# control-tu56v6.net
KiCad netlist of a schematic drawn in EAGLE
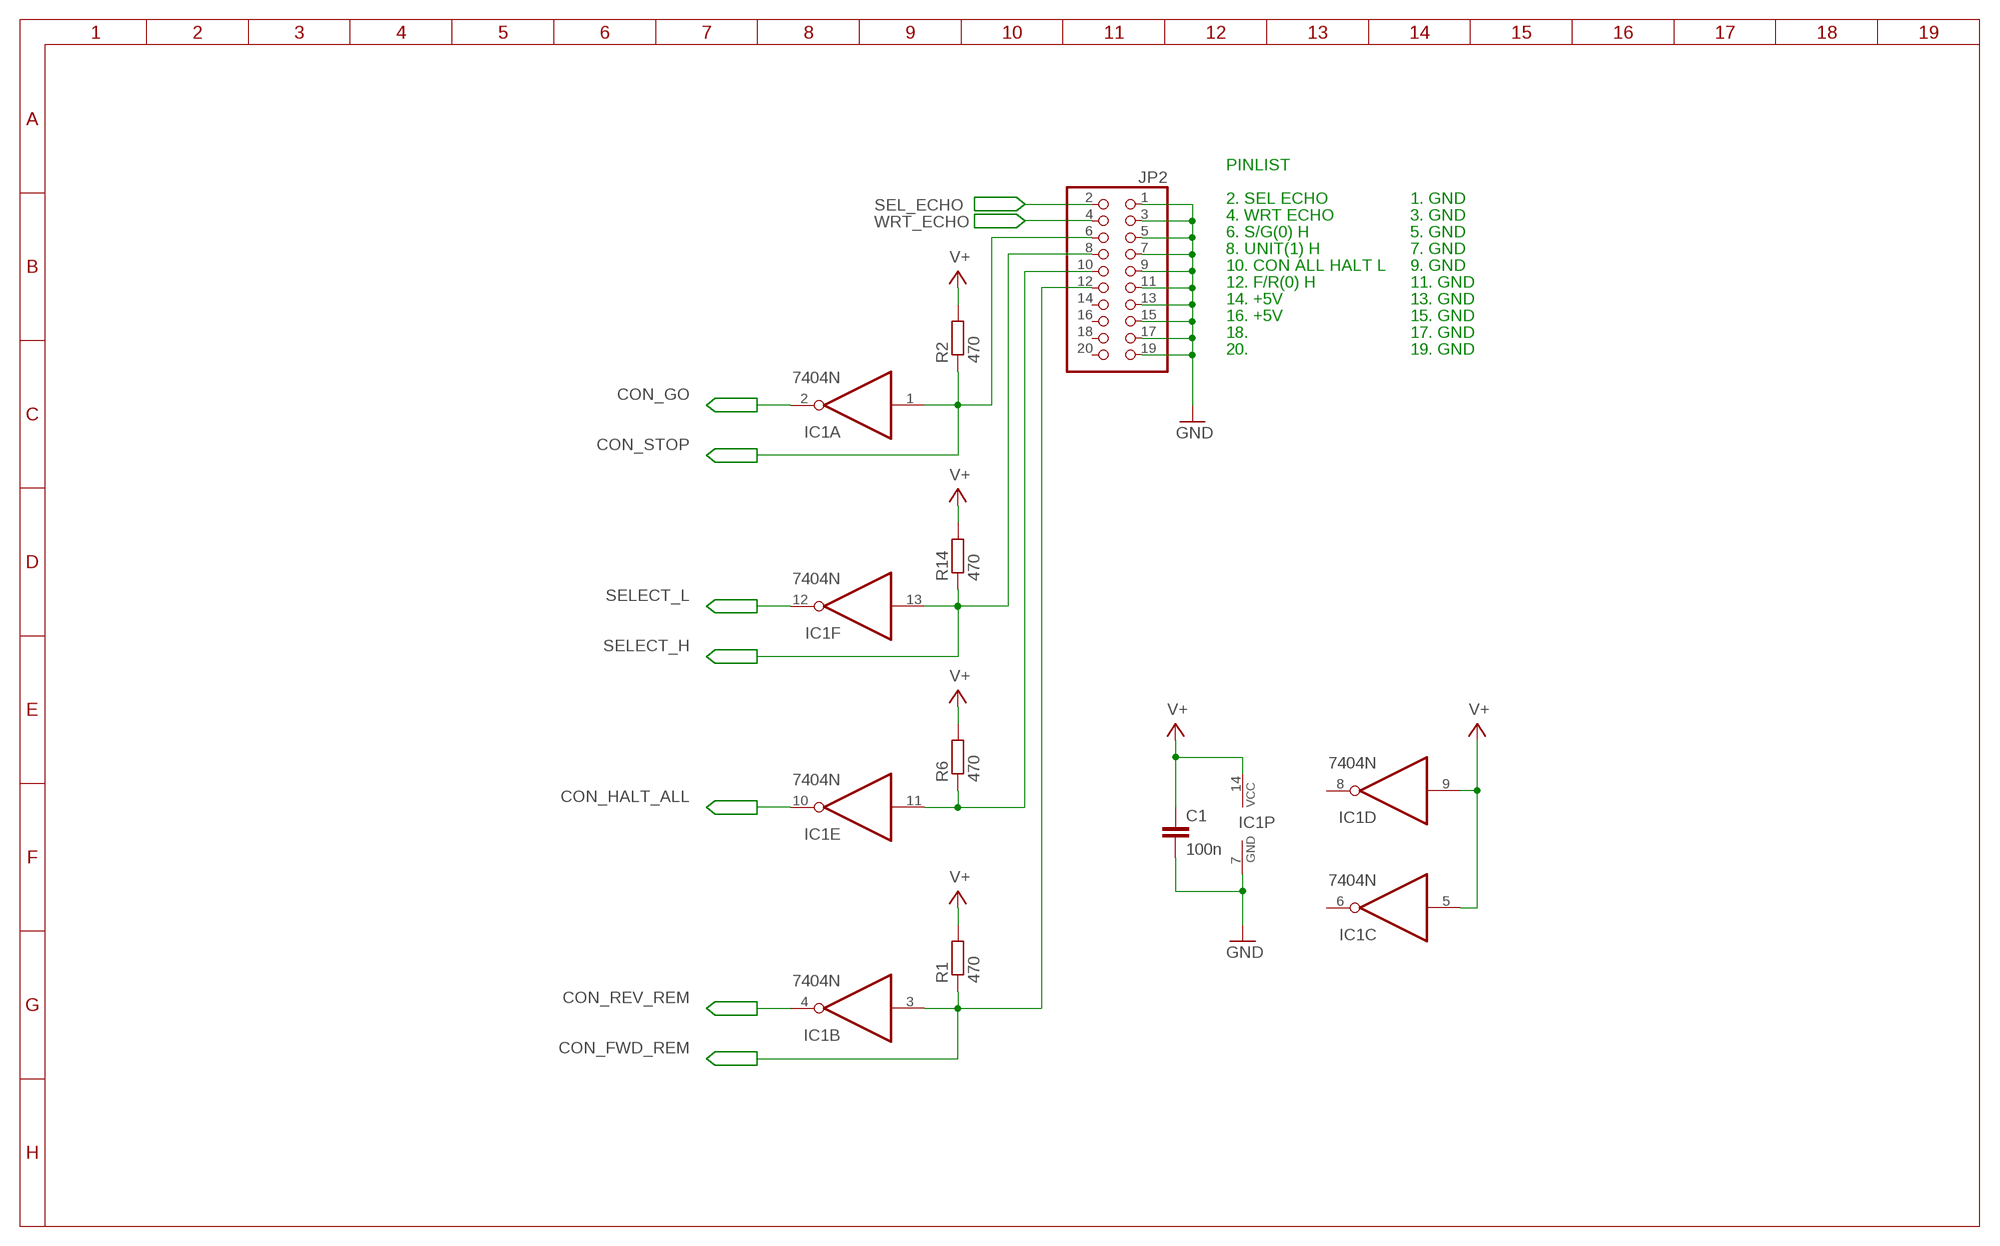
[diagram p0: schematic, sheet 1]
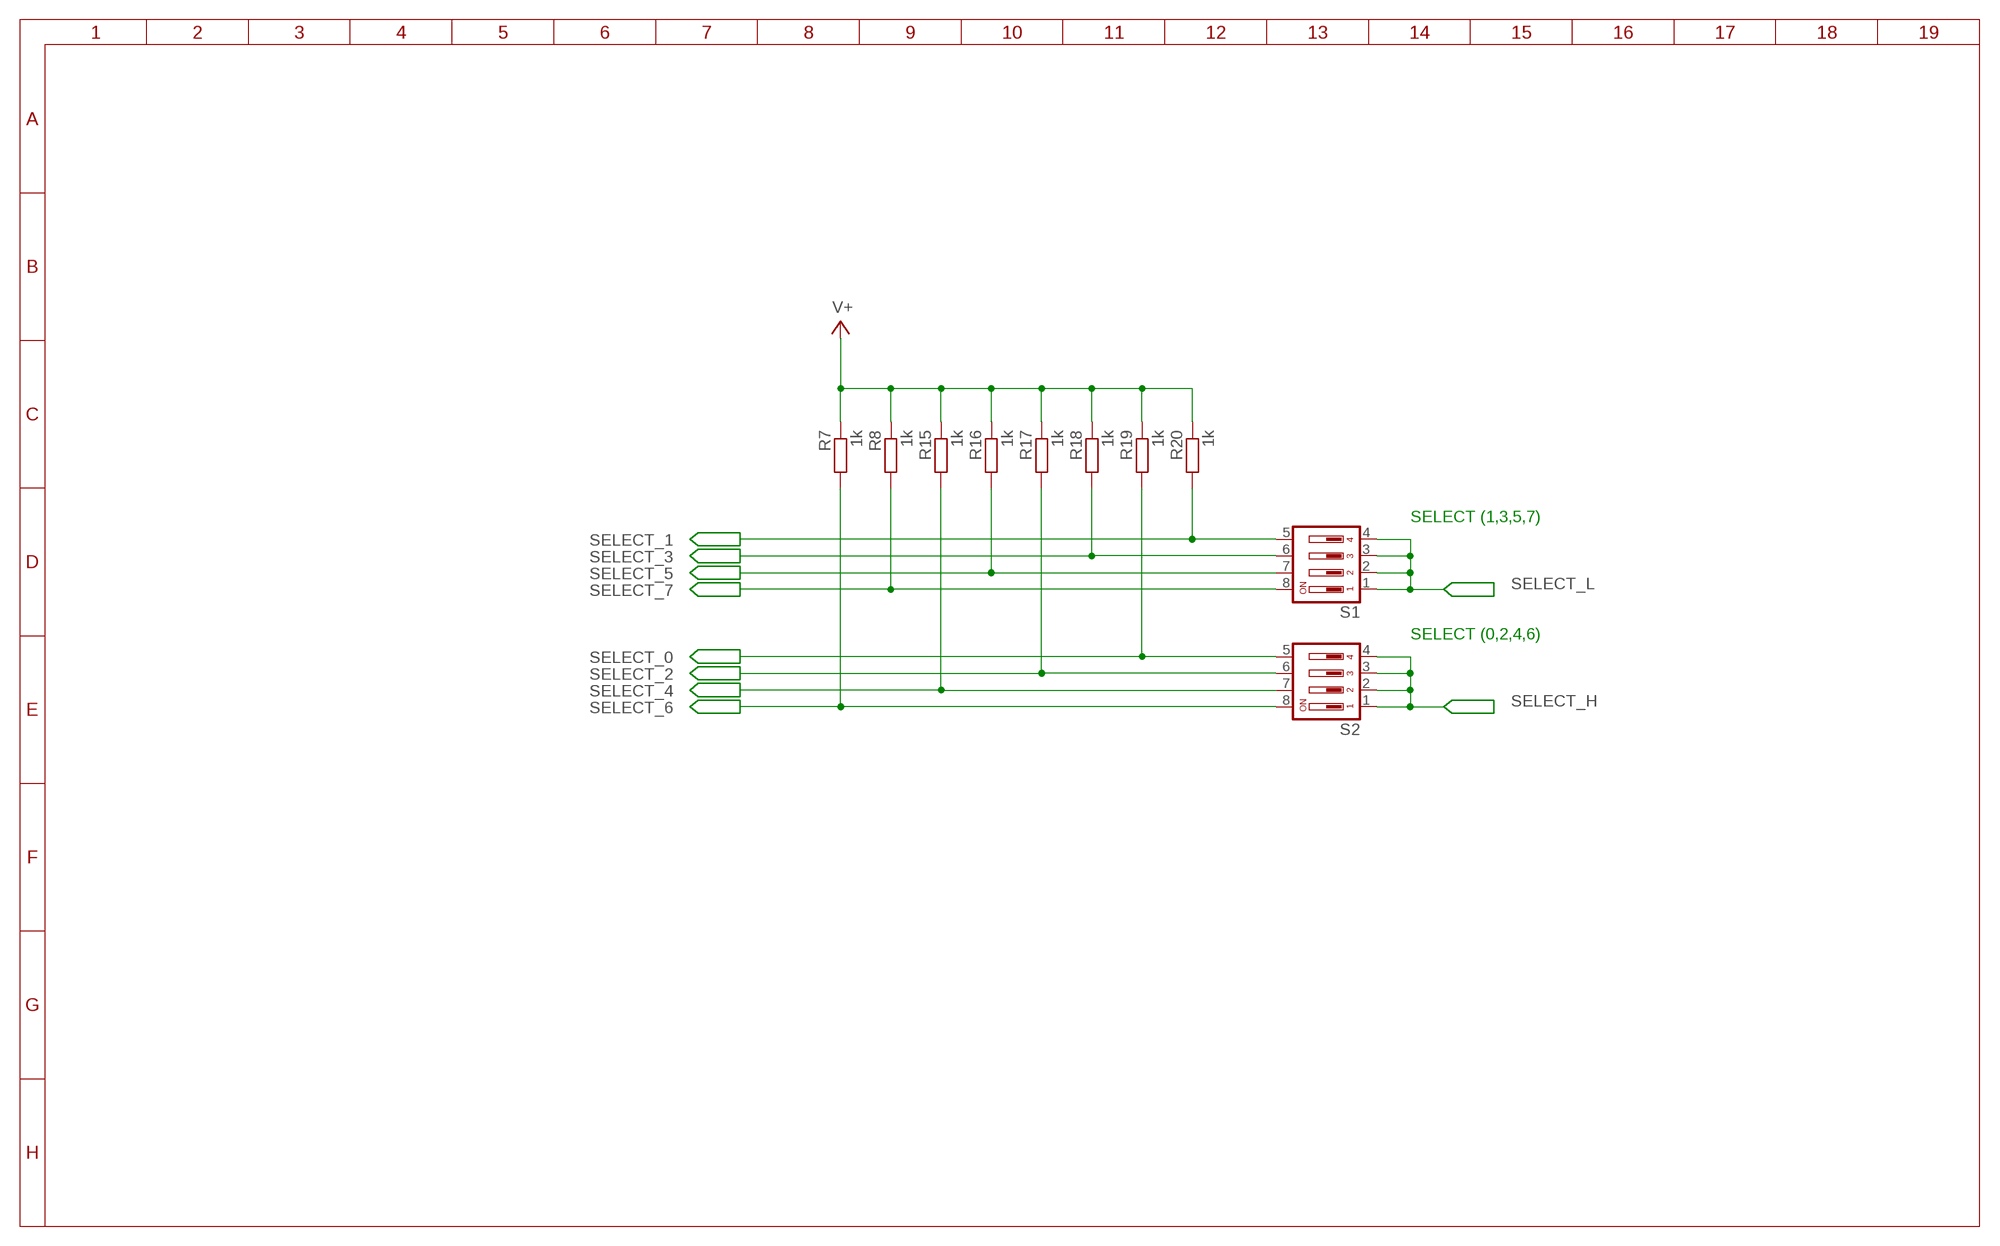
[diagram p1: schematic, sheet 2]
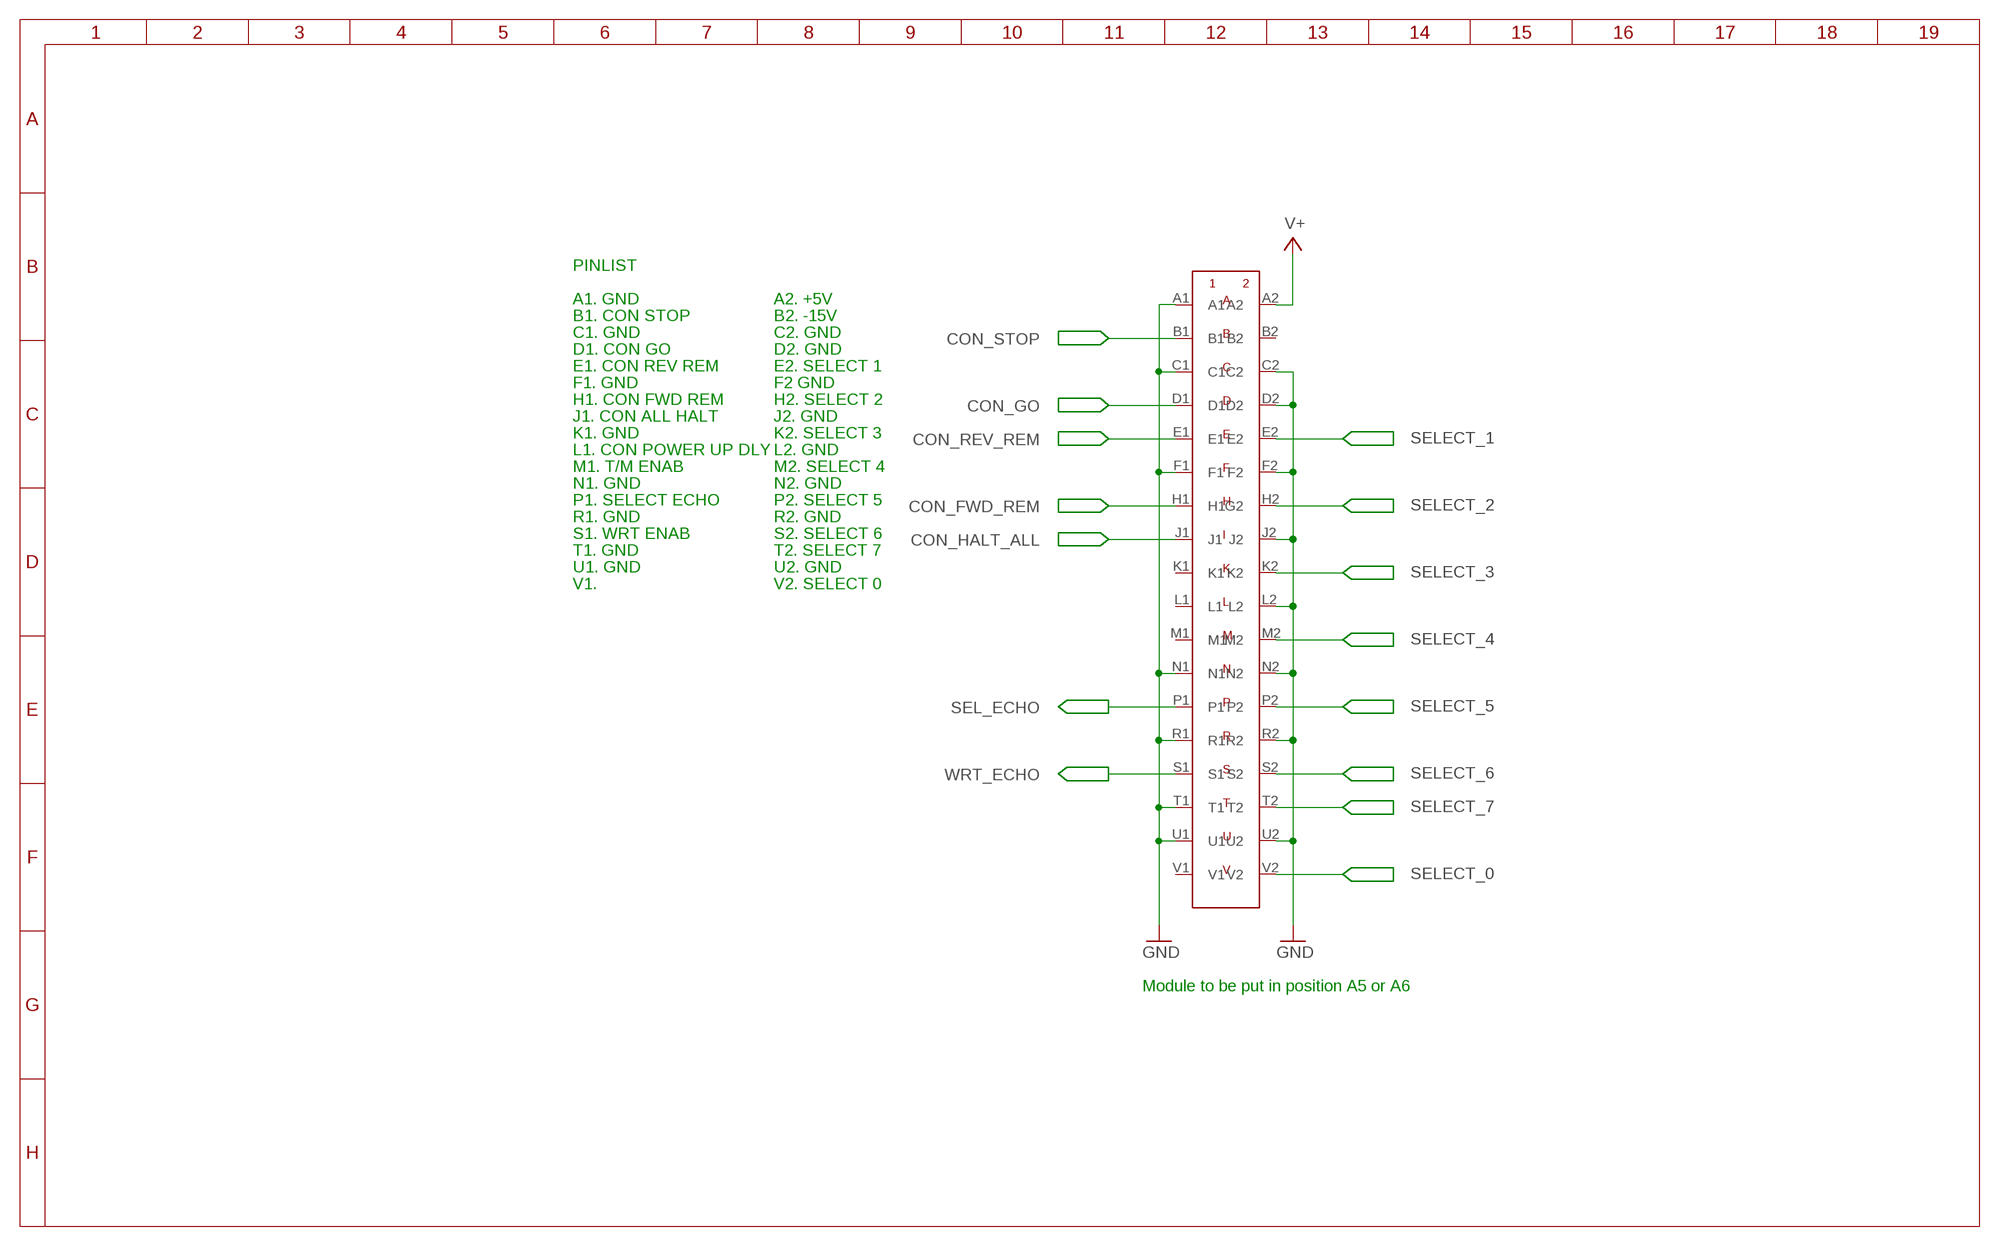
[diagram p2: schematic, sheet 3]

(export (version "E")
  (design (tool "Eeschema 10.0.6"))
  (components
    (comp (ref "CON1")
      (value "FLIPCHIP_1NORMAL")
      (footprint "eagle-import:FLIPCHIP-1")
      (libsource (lib "eagle-import") (part "FLIPCHIP_1NORMAL"))
    )
    (comp (ref "C1")
      (value "100n")
      (footprint "eagle-import:C5B3.5")
      (libsource (lib "eagle-import") (part "C5/3.5"))
    )
    (comp (ref "IC1")
      (value "7404N")
      (footprint "eagle-import:DIL14")
      (libsource (lib "eagle-import") (part "7404N"))
    )
    (comp (ref "JP2")
      (value "PINHD-2X10/90-FRAMED")
      (footprint "eagle-import:2Z10_90-FRAMED")
      (libsource (lib "eagle-import") (part "PINHD-2X10/90-FRAMED"))
    )
    (comp (ref "R1")
      (value "470")
      (footprint "eagle-import:0207_10")
      (libsource (lib "eagle-import") (part "R-EU_0207/10"))
    )
    (comp (ref "R2")
      (value "470")
      (footprint "eagle-import:0207_10")
      (libsource (lib "eagle-import") (part "R-EU_0207/10"))
    )
    (comp (ref "R6")
      (value "470")
      (footprint "eagle-import:0207_10")
      (libsource (lib "eagle-import") (part "R-EU_0207/10"))
    )
    (comp (ref "R14")
      (value "470")
      (footprint "eagle-import:0207_10")
      (libsource (lib "eagle-import") (part "R-EU_0207/10"))
    )
    (comp (ref "R7")
      (value "1k")
      (footprint "eagle-import:0207_10")
      (libsource (lib "eagle-import") (part "R-EU_0207/10"))
    )
    (comp (ref "R8")
      (value "1k")
      (footprint "eagle-import:0207_10")
      (libsource (lib "eagle-import") (part "R-EU_0207/10"))
    )
    (comp (ref "R15")
      (value "1k")
      (footprint "eagle-import:0207_10")
      (libsource (lib "eagle-import") (part "R-EU_0207/10"))
    )
    (comp (ref "R16")
      (value "1k")
      (footprint "eagle-import:0207_10")
      (libsource (lib "eagle-import") (part "R-EU_0207/10"))
    )
    (comp (ref "R17")
      (value "1k")
      (footprint "eagle-import:0207_10")
      (libsource (lib "eagle-import") (part "R-EU_0207/10"))
    )
    (comp (ref "R18")
      (value "1k")
      (footprint "eagle-import:0207_10")
      (libsource (lib "eagle-import") (part "R-EU_0207/10"))
    )
    (comp (ref "R19")
      (value "1k")
      (footprint "eagle-import:0207_10")
      (libsource (lib "eagle-import") (part "R-EU_0207/10"))
    )
    (comp (ref "R20")
      (value "1k")
      (footprint "eagle-import:0207_10")
      (libsource (lib "eagle-import") (part "R-EU_0207/10"))
    )
    (comp (ref "S1")
      (value "DIP04YL")
      (footprint "eagle-import:DIP04YL")
      (libsource (lib "eagle-import") (part "DIP04YL"))
    )
    (comp (ref "S2")
      (value "DIP04YL")
      (footprint "eagle-import:DIP04YL")
      (libsource (lib "eagle-import") (part "DIP04YL"))
    )
  )
  (nets
    (net (code "1") (name "CON_FWD_REM") (class "Default")
      (node (ref "CON1") (pin "H1") (pinfunction "H1_H1") (pintype "bidirectional"))
      (node (ref "IC1") (pin "3") (pinfunction "I_3") (pintype "input"))
      (node (ref "JP2") (pin "12") (pinfunction "12_12") (pintype "passive"))
      (node (ref "R1") (pin "1") (pinfunction "1_1") (pintype "passive"))
    )
    (net (code "2") (name "CON_GO") (class "Default")
      (node (ref "CON1") (pin "D1") (pinfunction "D1_D1") (pintype "bidirectional"))
      (node (ref "IC1") (pin "2") (pinfunction "O_2") (pintype "output"))
    )
    (net (code "3") (name "CON_HALT_ALL") (class "Default")
      (node (ref "CON1") (pin "J1") (pinfunction "J1_J1") (pintype "bidirectional"))
      (node (ref "IC1") (pin "10") (pinfunction "O_10") (pintype "output"))
    )
    (net (code "4") (name "CON_REV_REM") (class "Default")
      (node (ref "CON1") (pin "E1") (pinfunction "E1_E1") (pintype "bidirectional"))
      (node (ref "IC1") (pin "4") (pinfunction "O_4") (pintype "output"))
    )
    (net (code "5") (name "CON_STOP") (class "Default")
      (node (ref "CON1") (pin "B1") (pinfunction "B1_B1") (pintype "bidirectional"))
      (node (ref "IC1") (pin "1") (pinfunction "I_1") (pintype "input"))
      (node (ref "JP2") (pin "6") (pinfunction "6_6") (pintype "passive"))
      (node (ref "R2") (pin "1") (pinfunction "1_1") (pintype "passive"))
    )
    (net (code "6") (name "GND") (class "Default")
      (node (ref "C1") (pin "2") (pinfunction "2_2") (pintype "passive"))
      (node (ref "CON1") (pin "A1") (pinfunction "A1_A1") (pintype "bidirectional"))
      (node (ref "CON1") (pin "C1") (pinfunction "C1_C1") (pintype "bidirectional"))
      (node (ref "CON1") (pin "C2") (pinfunction "C2_C2") (pintype "bidirectional"))
      (node (ref "CON1") (pin "D2") (pinfunction "D2_D2") (pintype "bidirectional"))
      (node (ref "CON1") (pin "F1") (pinfunction "F1_F1") (pintype "bidirectional"))
      (node (ref "CON1") (pin "F2") (pinfunction "F2_F2") (pintype "bidirectional"))
      (node (ref "CON1") (pin "J2") (pinfunction "J2_J2") (pintype "bidirectional"))
      (node (ref "CON1") (pin "L2") (pinfunction "L2_L2") (pintype "bidirectional"))
      (node (ref "CON1") (pin "N1") (pinfunction "N1_N1") (pintype "bidirectional"))
      (node (ref "CON1") (pin "N2") (pinfunction "N2_N2") (pintype "bidirectional"))
      (node (ref "CON1") (pin "R1") (pinfunction "R1_R1") (pintype "bidirectional"))
      (node (ref "CON1") (pin "R2") (pinfunction "R2_R2") (pintype "bidirectional"))
      (node (ref "CON1") (pin "T1") (pinfunction "T1_T1") (pintype "bidirectional"))
      (node (ref "CON1") (pin "U1") (pinfunction "U1_U1") (pintype "bidirectional"))
      (node (ref "CON1") (pin "U2") (pinfunction "U2_U2") (pintype "bidirectional"))
      (node (ref "IC1") (pin "7") (pinfunction "GND_7") (pintype "power_in"))
      (node (ref "JP2") (pin "1") (pinfunction "1_1") (pintype "passive"))
      (node (ref "JP2") (pin "11") (pinfunction "11_11") (pintype "passive"))
      (node (ref "JP2") (pin "13") (pinfunction "13_13") (pintype "passive"))
      (node (ref "JP2") (pin "15") (pinfunction "15_15") (pintype "passive"))
      (node (ref "JP2") (pin "17") (pinfunction "17_17") (pintype "passive"))
      (node (ref "JP2") (pin "19") (pinfunction "19_19") (pintype "passive"))
      (node (ref "JP2") (pin "3") (pinfunction "3_3") (pintype "passive"))
      (node (ref "JP2") (pin "5") (pinfunction "5_5") (pintype "passive"))
      (node (ref "JP2") (pin "7") (pinfunction "7_7") (pintype "passive"))
      (node (ref "JP2") (pin "9") (pinfunction "9_9") (pintype "passive"))
    )
    (net (code "7") (name "Net-(IC1E-I)") (class "Default")
      (node (ref "IC1") (pin "11") (pinfunction "I_11") (pintype "input"))
      (node (ref "JP2") (pin "10") (pinfunction "10_10") (pintype "passive"))
      (node (ref "R6") (pin "1") (pinfunction "1_1") (pintype "passive"))
    )
    (net (code "8") (name "SELECT_0") (class "Default")
      (node (ref "CON1") (pin "V2") (pinfunction "V2_V2") (pintype "bidirectional"))
      (node (ref "R19") (pin "2") (pinfunction "2_2") (pintype "passive"))
      (node (ref "S2") (pin "5") (pinfunction "5_5") (pintype "passive"))
    )
    (net (code "9") (name "SELECT_1") (class "Default")
      (node (ref "CON1") (pin "E2") (pinfunction "E2_E2") (pintype "bidirectional"))
      (node (ref "R20") (pin "2") (pinfunction "2_2") (pintype "passive"))
      (node (ref "S1") (pin "5") (pinfunction "5_5") (pintype "passive"))
    )
    (net (code "10") (name "SELECT_2") (class "Default")
      (node (ref "CON1") (pin "H2") (pinfunction "G2_H2") (pintype "bidirectional"))
      (node (ref "R17") (pin "2") (pinfunction "2_2") (pintype "passive"))
      (node (ref "S2") (pin "6") (pinfunction "6_6") (pintype "passive"))
    )
    (net (code "11") (name "SELECT_3") (class "Default")
      (node (ref "CON1") (pin "K2") (pinfunction "K2_K2") (pintype "bidirectional"))
      (node (ref "R18") (pin "2") (pinfunction "2_2") (pintype "passive"))
      (node (ref "S1") (pin "6") (pinfunction "6_6") (pintype "passive"))
    )
    (net (code "12") (name "SELECT_4") (class "Default")
      (node (ref "CON1") (pin "M2") (pinfunction "M2_M2") (pintype "bidirectional"))
      (node (ref "R15") (pin "2") (pinfunction "2_2") (pintype "passive"))
      (node (ref "S2") (pin "7") (pinfunction "7_7") (pintype "passive"))
    )
    (net (code "13") (name "SELECT_5") (class "Default")
      (node (ref "CON1") (pin "P2") (pinfunction "P2_P2") (pintype "bidirectional"))
      (node (ref "R16") (pin "2") (pinfunction "2_2") (pintype "passive"))
      (node (ref "S1") (pin "7") (pinfunction "7_7") (pintype "passive"))
    )
    (net (code "14") (name "SELECT_6") (class "Default")
      (node (ref "CON1") (pin "S2") (pinfunction "S2_S2") (pintype "bidirectional"))
      (node (ref "R7") (pin "2") (pinfunction "2_2") (pintype "passive"))
      (node (ref "S2") (pin "8") (pinfunction "8_8") (pintype "passive"))
    )
    (net (code "15") (name "SELECT_7") (class "Default")
      (node (ref "CON1") (pin "T2") (pinfunction "T2_T2") (pintype "bidirectional"))
      (node (ref "R8") (pin "2") (pinfunction "2_2") (pintype "passive"))
      (node (ref "S1") (pin "8") (pinfunction "8_8") (pintype "passive"))
    )
    (net (code "16") (name "SELECT_H") (class "Default")
      (node (ref "IC1") (pin "13") (pinfunction "I_13") (pintype "input"))
      (node (ref "JP2") (pin "8") (pinfunction "8_8") (pintype "passive"))
      (node (ref "R14") (pin "1") (pinfunction "1_1") (pintype "passive"))
      (node (ref "S2") (pin "1") (pinfunction "1_1") (pintype "passive"))
      (node (ref "S2") (pin "2") (pinfunction "2_2") (pintype "passive"))
      (node (ref "S2") (pin "3") (pinfunction "3_3") (pintype "passive"))
      (node (ref "S2") (pin "4") (pinfunction "4_4") (pintype "passive"))
    )
    (net (code "17") (name "SELECT_L") (class "Default")
      (node (ref "IC1") (pin "12") (pinfunction "O_12") (pintype "output"))
      (node (ref "S1") (pin "1") (pinfunction "1_1") (pintype "passive"))
      (node (ref "S1") (pin "2") (pinfunction "2_2") (pintype "passive"))
      (node (ref "S1") (pin "3") (pinfunction "3_3") (pintype "passive"))
      (node (ref "S1") (pin "4") (pinfunction "4_4") (pintype "passive"))
    )
    (net (code "18") (name "SEL_ECHO") (class "Default")
      (node (ref "CON1") (pin "P1") (pinfunction "P1_P1") (pintype "bidirectional"))
      (node (ref "JP2") (pin "2") (pinfunction "2_2") (pintype "passive"))
    )
    (net (code "19") (name "V+") (class "Default")
      (node (ref "C1") (pin "1") (pinfunction "1_1") (pintype "passive"))
      (node (ref "CON1") (pin "A2") (pinfunction "A2_A2") (pintype "bidirectional"))
      (node (ref "IC1") (pin "14") (pinfunction "VCC_14") (pintype "power_in"))
      (node (ref "IC1") (pin "5") (pinfunction "I_5") (pintype "input"))
      (node (ref "IC1") (pin "9") (pinfunction "I_9") (pintype "input"))
      (node (ref "R1") (pin "2") (pinfunction "2_2") (pintype "passive"))
      (node (ref "R14") (pin "2") (pinfunction "2_2") (pintype "passive"))
      (node (ref "R15") (pin "1") (pinfunction "1_1") (pintype "passive"))
      (node (ref "R16") (pin "1") (pinfunction "1_1") (pintype "passive"))
      (node (ref "R17") (pin "1") (pinfunction "1_1") (pintype "passive"))
      (node (ref "R18") (pin "1") (pinfunction "1_1") (pintype "passive"))
      (node (ref "R19") (pin "1") (pinfunction "1_1") (pintype "passive"))
      (node (ref "R2") (pin "2") (pinfunction "2_2") (pintype "passive"))
      (node (ref "R20") (pin "1") (pinfunction "1_1") (pintype "passive"))
      (node (ref "R6") (pin "2") (pinfunction "2_2") (pintype "passive"))
      (node (ref "R7") (pin "1") (pinfunction "1_1") (pintype "passive"))
      (node (ref "R8") (pin "1") (pinfunction "1_1") (pintype "passive"))
    )
    (net (code "20") (name "WRT_ECHO") (class "Default")
      (node (ref "CON1") (pin "S1") (pinfunction "S1_S1") (pintype "bidirectional"))
      (node (ref "JP2") (pin "4") (pinfunction "4_4") (pintype "passive"))
    )
    (net (code "21") (name "unconnected-(CON1-PadB2)") (class "Default")
      (node (ref "CON1") (pin "B2") (pinfunction "B2_B2") (pintype "bidirectional"))
    )
    (net (code "22") (name "unconnected-(CON1-PadK1)") (class "Default")
      (node (ref "CON1") (pin "K1") (pinfunction "K1_K1") (pintype "bidirectional"))
    )
    (net (code "23") (name "unconnected-(CON1-PadL1)") (class "Default")
      (node (ref "CON1") (pin "L1") (pinfunction "L1_L1") (pintype "bidirectional"))
    )
    (net (code "24") (name "unconnected-(CON1-PadM1)") (class "Default")
      (node (ref "CON1") (pin "M1") (pinfunction "M1_M1") (pintype "bidirectional"))
    )
    (net (code "25") (name "unconnected-(CON1-PadV1)") (class "Default")
      (node (ref "CON1") (pin "V1") (pinfunction "V1_V1") (pintype "bidirectional"))
    )
    (net (code "26") (name "unconnected-(IC1C-O-Pad6)") (class "Default")
      (node (ref "IC1") (pin "6") (pinfunction "O_6") (pintype "output"))
    )
    (net (code "27") (name "unconnected-(IC1D-O-Pad8)") (class "Default")
      (node (ref "IC1") (pin "8") (pinfunction "O_8") (pintype "output"))
    )
    (net (code "28") (name "unconnected-(JP2-Pad14)") (class "Default")
      (node (ref "JP2") (pin "14") (pinfunction "14_14") (pintype "passive"))
    )
    (net (code "29") (name "unconnected-(JP2-Pad16)") (class "Default")
      (node (ref "JP2") (pin "16") (pinfunction "16_16") (pintype "passive"))
    )
    (net (code "30") (name "unconnected-(JP2-Pad18)") (class "Default")
      (node (ref "JP2") (pin "18") (pinfunction "18_18") (pintype "passive"))
    )
    (net (code "31") (name "unconnected-(JP2-Pad20)") (class "Default")
      (node (ref "JP2") (pin "20") (pinfunction "20_20") (pintype "passive"))
    )
  )
)
